# SIM800L.net
KiCad netlist of a schematic drawn in Altium Designer
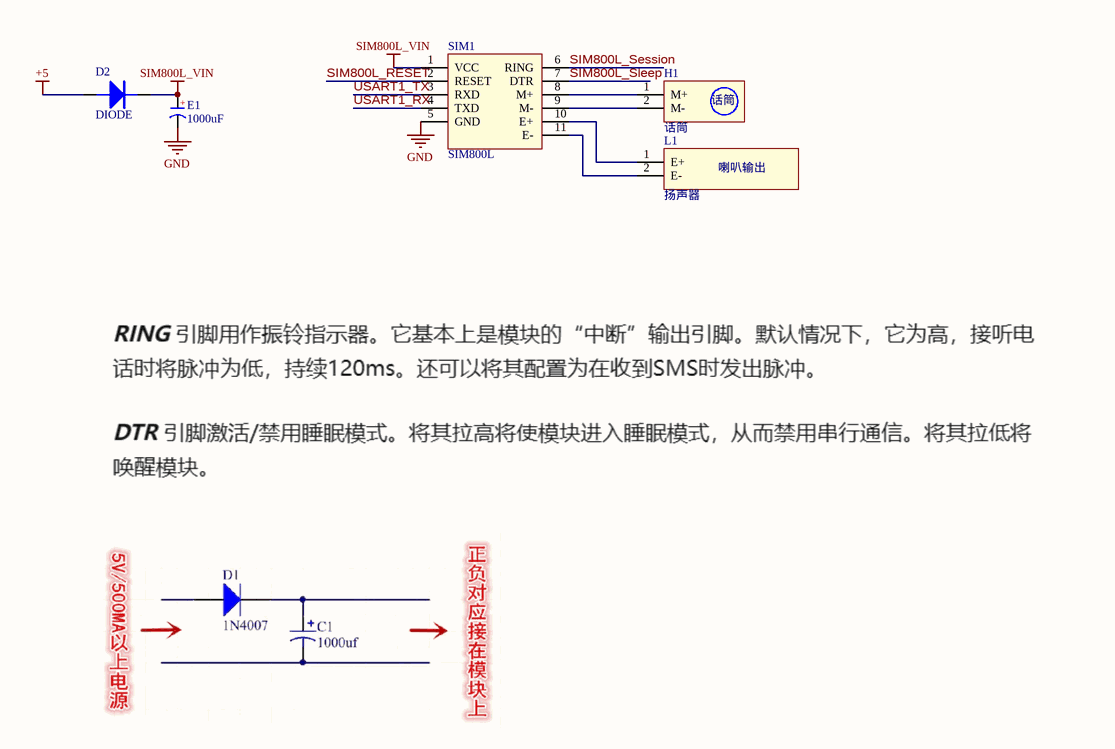
[diagram p0: SIM800L.SchDoc]

(export (version "E")
  (design (tool "Eeschema 10.0.6"))
  (components
    (comp (ref "D2")
      (value "DIODE")
      (footprint "DO-15")
      (description "普通二极管")
      (libsource (lib "二极管") (part "DIODE"))
    )
    (comp (ref "E1")
      (value "1000uF")
      (footprint "CAP 1.5*4*8")
      (description "直插电解电容")
      (fields (field (name "版权归属") "源创客"))
      (libsource (lib "3.1   - 电阻-电容-电感") (part "C-CAP"))
    )
    (comp (ref "H1") (value "话筒") (footprint "话筒") (libsource (lib "STM32_Phone_2") (part "话筒")))
    (comp (ref "L1") (value "扬声器") (footprint "扬声器") (libsource (lib "STM32_Phone") (part "扬声器")))
    (comp (ref "SIM1")
      (value "SIM800L")
      (footprint "SIM800L")
      (libsource (lib "STM32_Phone") (part "SIM800L"))
    )
  )
  (nets
    (net (code "1") (name "+5") (class "Default")
      (node (ref "D2") (pin "A") (pinfunction "A_A") (pintype "passive"))
    )
    (net (code "2") (name "/SIM800L_RESET") (class "Default")
      (node (ref "SIM1") (pin "2") (pinfunction "RESET_2") (pintype "passive"))
    )
    (net (code "3") (name "/SIM800L_Session") (class "Default")
      (node (ref "SIM1") (pin "6") (pinfunction "RING_6") (pintype "passive"))
    )
    (net (code "4") (name "/SIM800L_Sleep") (class "Default")
      (node (ref "SIM1") (pin "7") (pinfunction "DTR_7") (pintype "passive"))
    )
    (net (code "5") (name "/USART1_RX") (class "Default")
      (node (ref "SIM1") (pin "4") (pinfunction "TXD_4") (pintype "passive"))
    )
    (net (code "6") (name "/USART1_TX") (class "Default")
      (node (ref "SIM1") (pin "3") (pinfunction "RXD_3") (pintype "passive"))
    )
    (net (code "7") (name "GND") (class "Default")
      (node (ref "E1") (pin "2") (pinfunction "K_2") (pintype "passive"))
      (node (ref "SIM1") (pin "5") (pinfunction "GND_5") (pintype "passive"))
    )
    (net (code "8") (name "Net-(H1-M+)") (class "Default")
      (node (ref "H1") (pin "1") (pinfunction "M+_1") (pintype "passive"))
      (node (ref "SIM1") (pin "8") (pinfunction "M+_8") (pintype "passive"))
    )
    (net (code "9") (name "Net-(H1-M-)") (class "Default")
      (node (ref "H1") (pin "2") (pinfunction "M-_2") (pintype "passive"))
      (node (ref "SIM1") (pin "9") (pinfunction "M-_9") (pintype "passive"))
    )
    (net (code "10") (name "Net-(L1-E+)") (class "Default")
      (node (ref "L1") (pin "1") (pinfunction "E+_1") (pintype "passive"))
      (node (ref "SIM1") (pin "10") (pinfunction "E+_10") (pintype "passive"))
    )
    (net (code "11") (name "Net-(L1-E-)") (class "Default")
      (node (ref "L1") (pin "2") (pinfunction "E-_2") (pintype "passive"))
      (node (ref "SIM1") (pin "11") (pinfunction "E-_11") (pintype "passive"))
    )
    (net (code "12") (name "SIM800L_VIN") (class "Default")
      (node (ref "D2") (pin "K") (pinfunction "K_K") (pintype "passive"))
      (node (ref "E1") (pin "1") (pinfunction "A_1") (pintype "passive"))
      (node (ref "SIM1") (pin "1") (pinfunction "VCC_1") (pintype "passive"))
    )
  )
)
